# laser_scanner.net
KiCad netlist of a schematic drawn in EAGLE
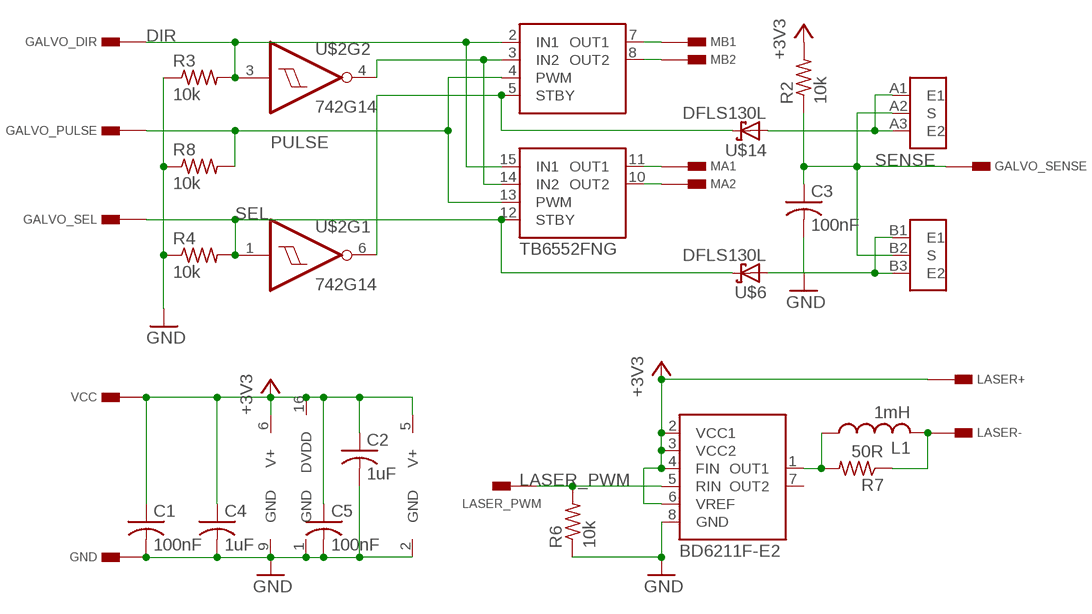
[diagram p0: schematic, sheet 1]

(export (version "E")
  (design (tool "Eeschema 10.0.6"))
  (components
    (comp (ref "C1")
      (value "100nF")
      (footprint "eagle-import:C0603")
      (libsource (lib "eagle-import") (part "C-USC0603"))
    )
    (comp (ref "C2")
      (value "1uF")
      (footprint "eagle-import:C0603")
      (libsource (lib "eagle-import") (part "C-USC0603"))
    )
    (comp (ref "C3")
      (value "100nF")
      (footprint "eagle-import:C0603")
      (libsource (lib "eagle-import") (part "C-USC0603"))
    )
    (comp (ref "C4")
      (value "1uF")
      (footprint "eagle-import:C0603")
      (libsource (lib "eagle-import") (part "C-USC0603"))
    )
    (comp (ref "C5")
      (value "100nF")
      (footprint "eagle-import:C0603")
      (libsource (lib "eagle-import") (part "C-USC0603"))
    )
    (comp (ref "GALVO_DIR")
      (value "PAD-0.6_1.8")
      (footprint "eagle-import:PAD_0.6_1.8")
      (libsource (lib "eagle-import") (part "PAD-0.6_1.8"))
    )
    (comp (ref "GALVO_PULSE")
      (value "PAD-0.6_1.8")
      (footprint "eagle-import:PAD_0.6_1.8")
      (libsource (lib "eagle-import") (part "PAD-0.6_1.8"))
    )
    (comp (ref "GALVO_SEL")
      (value "PAD-0.6_1.8")
      (footprint "eagle-import:PAD_0.6_1.8")
      (libsource (lib "eagle-import") (part "PAD-0.6_1.8"))
    )
    (comp (ref "GALVO_SENSE")
      (value "PAD-0.6_1.8")
      (footprint "eagle-import:PAD_0.6_1.8")
      (libsource (lib "eagle-import") (part "PAD-0.6_1.8"))
    )
    (comp (ref "GND")
      (value "PAD-0.6_1.8")
      (footprint "eagle-import:PAD_0.6_1.8")
      (libsource (lib "eagle-import") (part "PAD-0.6_1.8"))
    )
    (comp (ref "L1")
      (value "1mH")
      (footprint "eagle-import:L7070")
      (libsource (lib "eagle-import") (part "L-US"))
    )
    (comp (ref "LASER+")
      (value "PAD-0.6_1.8")
      (footprint "eagle-import:PAD_0.6_1.8")
      (libsource (lib "eagle-import") (part "PAD-0.6_1.8"))
    )
    (comp (ref "LASER-")
      (value "PAD-0.6_1.8")
      (footprint "eagle-import:PAD_0.6_1.8")
      (libsource (lib "eagle-import") (part "PAD-0.6_1.8"))
    )
    (comp (ref "LASER_PWM")
      (value "PAD-0.6_1.8")
      (footprint "eagle-import:PAD_0.6_1.8")
      (libsource (lib "eagle-import") (part "PAD-0.6_1.8"))
    )
    (comp (ref "MA1")
      (value "PAD-0.6_1.8")
      (footprint "eagle-import:PAD_0.6_1.8")
      (libsource (lib "eagle-import") (part "PAD-0.6_1.8"))
    )
    (comp (ref "MA2")
      (value "PAD-0.6_1.8")
      (footprint "eagle-import:PAD_0.6_1.8")
      (libsource (lib "eagle-import") (part "PAD-0.6_1.8"))
    )
    (comp (ref "MB1")
      (value "PAD-0.6_1.8")
      (footprint "eagle-import:PAD_0.6_1.8")
      (libsource (lib "eagle-import") (part "PAD-0.6_1.8"))
    )
    (comp (ref "MB2")
      (value "PAD-0.6_1.8")
      (footprint "eagle-import:PAD_0.6_1.8")
      (libsource (lib "eagle-import") (part "PAD-0.6_1.8"))
    )
    (comp (ref "R2")
      (value "10k")
      (footprint "eagle-import:R0603")
      (libsource (lib "eagle-import") (part "R-US_R0603"))
    )
    (comp (ref "R3")
      (value "10k")
      (footprint "eagle-import:R0603")
      (libsource (lib "eagle-import") (part "R-US_R0603"))
    )
    (comp (ref "R4")
      (value "10k")
      (footprint "eagle-import:R0603")
      (libsource (lib "eagle-import") (part "R-US_R0603"))
    )
    (comp (ref "R6")
      (value "10k")
      (footprint "eagle-import:R0603")
      (libsource (lib "eagle-import") (part "R-US_R0603"))
    )
    (comp (ref "R7")
      (value "50R")
      (footprint "eagle-import:R0603")
      (libsource (lib "eagle-import") (part "R-US_R0603"))
    )
    (comp (ref "R8")
      (value "10k")
      (footprint "eagle-import:R0603")
      (libsource (lib "eagle-import") (part "R-US_R0603"))
    )
    (comp (ref "U$1")
      (value "TB6552")
      (footprint "eagle-import:TSSOP16")
      (libsource (lib "eagle-import") (part "TB6552"))
    )
    (comp (ref "U$2")
      (value "742G14")
      (footprint "eagle-import:SOT23-6")
      (libsource (lib "eagle-import") (part "742G14"))
    )
    (comp (ref "U$3")
      (value "BD6211")
      (footprint "eagle-import:SOP-08")
      (libsource (lib "eagle-import") (part "BD6211"))
    )
    (comp (ref "U$6")
      (value "DFLS130L")
      (footprint "eagle-import:POWERDI323")
      (libsource (lib "eagle-import") (part "DFLS130L"))
    )
    (comp (ref "U$7")
      (value "LASER_SLIDER")
      (footprint "eagle-import:LASER_SCANNER")
      (libsource (lib "eagle-import") (part "LASER_SLIDER"))
    )
    (comp (ref "U$14")
      (value "DFLS130L")
      (footprint "eagle-import:POWERDI323")
      (libsource (lib "eagle-import") (part "DFLS130L"))
    )
    (comp (ref "VCC")
      (value "PAD-0.6_1.8")
      (footprint "eagle-import:PAD_0.6_1.8")
      (libsource (lib "eagle-import") (part "PAD-0.6_1.8"))
    )
  )
  (nets
    (net (code "1") (name "+3V3") (class "Default")
      (node (ref "C1") (pin "1") (pinfunction "1_1") (pintype "passive"))
      (node (ref "C2") (pin "1") (pinfunction "1_1") (pintype "passive"))
      (node (ref "C4") (pin "1") (pinfunction "1_1") (pintype "passive"))
      (node (ref "C5") (pin "1") (pinfunction "1_1") (pintype "passive"))
      (node (ref "LASER+") (pin "1") (pinfunction "1_1") (pintype "bidirectional"))
      (node (ref "R2") (pin "2") (pinfunction "2_2") (pintype "passive"))
      (node (ref "U$1") (pin "16") (pinfunction "DVDD_16") (pintype "bidirectional"))
      (node (ref "U$1") (pin "6") (pinfunction "V+_6") (pintype "power_in"))
      (node (ref "U$2") (pin "5") (pinfunction "V+_5") (pintype "power_in"))
      (node (ref "U$3") (pin "2") (pinfunction "VCC1_2") (pintype "bidirectional"))
      (node (ref "U$3") (pin "3") (pinfunction "VCC2_3") (pintype "bidirectional"))
      (node (ref "U$3") (pin "4") (pinfunction "FIN_4") (pintype "bidirectional"))
      (node (ref "U$3") (pin "6") (pinfunction "VREF_6") (pintype "bidirectional"))
      (node (ref "VCC") (pin "1") (pinfunction "1_1") (pintype "bidirectional"))
    )
    (net (code "2") (name "/DIR") (class "Default")
      (node (ref "GALVO_DIR") (pin "1") (pinfunction "1_1") (pintype "bidirectional"))
      (node (ref "R3") (pin "2") (pinfunction "2_2") (pintype "passive"))
      (node (ref "U$1") (pin "15") (pinfunction "IN1_15") (pintype "bidirectional"))
      (node (ref "U$1") (pin "2") (pinfunction "IN1_2") (pintype "bidirectional"))
      (node (ref "U$2") (pin "3") (pinfunction "I_3") (pintype "input"))
    )
    (net (code "3") (name "/LASER_PWM") (class "Default")
      (node (ref "LASER_PWM") (pin "1") (pinfunction "1_1") (pintype "bidirectional"))
      (node (ref "R6") (pin "2") (pinfunction "2_2") (pintype "passive"))
      (node (ref "U$3") (pin "5") (pinfunction "RIN_5") (pintype "bidirectional"))
    )
    (net (code "4") (name "/PULSE") (class "Default")
      (node (ref "GALVO_PULSE") (pin "1") (pinfunction "1_1") (pintype "bidirectional"))
      (node (ref "R8") (pin "2") (pinfunction "2_2") (pintype "passive"))
      (node (ref "U$1") (pin "13") (pinfunction "PWM_13") (pintype "bidirectional"))
      (node (ref "U$1") (pin "4") (pinfunction "PWM_4") (pintype "bidirectional"))
    )
    (net (code "5") (name "/SEL") (class "Default")
      (node (ref "GALVO_SEL") (pin "1") (pinfunction "1_1") (pintype "bidirectional"))
      (node (ref "R4") (pin "2") (pinfunction "2_2") (pintype "passive"))
      (node (ref "U$1") (pin "12") (pinfunction "STBY_12") (pintype "bidirectional"))
      (node (ref "U$2") (pin "1") (pinfunction "I_1") (pintype "input"))
      (node (ref "U$6") (pin "C") (pinfunction "C_C") (pintype "passive"))
    )
    (net (code "6") (name "/SENSE") (class "Default")
      (node (ref "C3") (pin "1") (pinfunction "1_1") (pintype "passive"))
      (node (ref "GALVO_SENSE") (pin "1") (pinfunction "1_1") (pintype "bidirectional"))
      (node (ref "R2") (pin "1") (pinfunction "1_1") (pintype "passive"))
      (node (ref "U$7") (pin "A2") (pinfunction "S_A2") (pintype "bidirectional"))
      (node (ref "U$7") (pin "B2") (pinfunction "S_B2") (pintype "bidirectional"))
    )
    (net (code "7") (name "GND") (class "Default")
      (node (ref "C1") (pin "2") (pinfunction "2_2") (pintype "passive"))
      (node (ref "C2") (pin "2") (pinfunction "2_2") (pintype "passive"))
      (node (ref "C3") (pin "2") (pinfunction "2_2") (pintype "passive"))
      (node (ref "C4") (pin "2") (pinfunction "2_2") (pintype "passive"))
      (node (ref "C5") (pin "2") (pinfunction "2_2") (pintype "passive"))
      (node (ref "GND") (pin "1") (pinfunction "1_1") (pintype "bidirectional"))
      (node (ref "R3") (pin "1") (pinfunction "1_1") (pintype "passive"))
      (node (ref "R4") (pin "1") (pinfunction "1_1") (pintype "passive"))
      (node (ref "R6") (pin "1") (pinfunction "1_1") (pintype "passive"))
      (node (ref "R8") (pin "1") (pinfunction "1_1") (pintype "passive"))
      (node (ref "U$1") (pin "1") (pinfunction "GND_1") (pintype "bidirectional"))
      (node (ref "U$1") (pin "9") (pinfunction "GND_9") (pintype "power_in"))
      (node (ref "U$2") (pin "2") (pinfunction "GND_2") (pintype "power_in"))
      (node (ref "U$3") (pin "8") (pinfunction "GND_8") (pintype "bidirectional"))
    )
    (net (code "8") (name "Net-(L1-Pad2)") (class "Default")
      (node (ref "L1") (pin "2") (pinfunction "2_2") (pintype "passive"))
      (node (ref "LASER-") (pin "1") (pinfunction "1_1") (pintype "bidirectional"))
      (node (ref "R7") (pin "1") (pinfunction "1_1") (pintype "passive"))
    )
    (net (code "9") (name "Net-(U$1A-IN2)") (class "Default")
      (node (ref "U$1") (pin "14") (pinfunction "IN2_14") (pintype "bidirectional"))
      (node (ref "U$1") (pin "3") (pinfunction "IN2_3") (pintype "bidirectional"))
      (node (ref "U$2") (pin "4") (pinfunction "O_4") (pintype "output"))
    )
    (net (code "10") (name "Net-(U$1A-OUT1)") (class "Default")
      (node (ref "MB1") (pin "1") (pinfunction "1_1") (pintype "bidirectional"))
      (node (ref "U$1") (pin "7") (pinfunction "OUT1_7") (pintype "bidirectional"))
    )
    (net (code "11") (name "Net-(U$1A-OUT2)") (class "Default")
      (node (ref "MB2") (pin "1") (pinfunction "1_1") (pintype "bidirectional"))
      (node (ref "U$1") (pin "8") (pinfunction "OUT2_8") (pintype "bidirectional"))
    )
    (net (code "12") (name "Net-(U$1A-STBY)") (class "Default")
      (node (ref "U$1") (pin "5") (pinfunction "STBY_5") (pintype "bidirectional"))
      (node (ref "U$14") (pin "C") (pinfunction "C_C") (pintype "passive"))
      (node (ref "U$2") (pin "6") (pinfunction "O_6") (pintype "output"))
    )
    (net (code "13") (name "Net-(U$1B-OUT1)") (class "Default")
      (node (ref "MA1") (pin "1") (pinfunction "1_1") (pintype "bidirectional"))
      (node (ref "U$1") (pin "11") (pinfunction "OUT1_11") (pintype "bidirectional"))
    )
    (net (code "14") (name "Net-(U$1B-OUT2)") (class "Default")
      (node (ref "MA2") (pin "1") (pinfunction "1_1") (pintype "bidirectional"))
      (node (ref "U$1") (pin "10") (pinfunction "OUT2_10") (pintype "bidirectional"))
    )
    (net (code "15") (name "Net-(U$3-OUT1)") (class "Default")
      (node (ref "L1") (pin "1") (pinfunction "1_1") (pintype "passive"))
      (node (ref "R7") (pin "2") (pinfunction "2_2") (pintype "passive"))
      (node (ref "U$3") (pin "1") (pinfunction "OUT1_1") (pintype "bidirectional"))
    )
    (net (code "16") (name "Net-(U$7A-E1)") (class "Default")
      (node (ref "U$14") (pin "A") (pinfunction "A_A") (pintype "passive"))
      (node (ref "U$7") (pin "A1") (pinfunction "E1_A1") (pintype "bidirectional"))
      (node (ref "U$7") (pin "A3") (pinfunction "E2_A3") (pintype "bidirectional"))
    )
    (net (code "17") (name "Net-(U$7B-E1)") (class "Default")
      (node (ref "U$6") (pin "A") (pinfunction "A_A") (pintype "passive"))
      (node (ref "U$7") (pin "B1") (pinfunction "E1_B1") (pintype "bidirectional"))
      (node (ref "U$7") (pin "B3") (pinfunction "E2_B3") (pintype "bidirectional"))
    )
    (net (code "18") (name "unconnected-(U$3-OUT2-Pad7)") (class "Default")
      (node (ref "U$3") (pin "7") (pinfunction "OUT2_7") (pintype "bidirectional"))
    )
  )
)
